# PWM_CON_CPU.net
KiCad netlist of a schematic drawn in Altium Designer
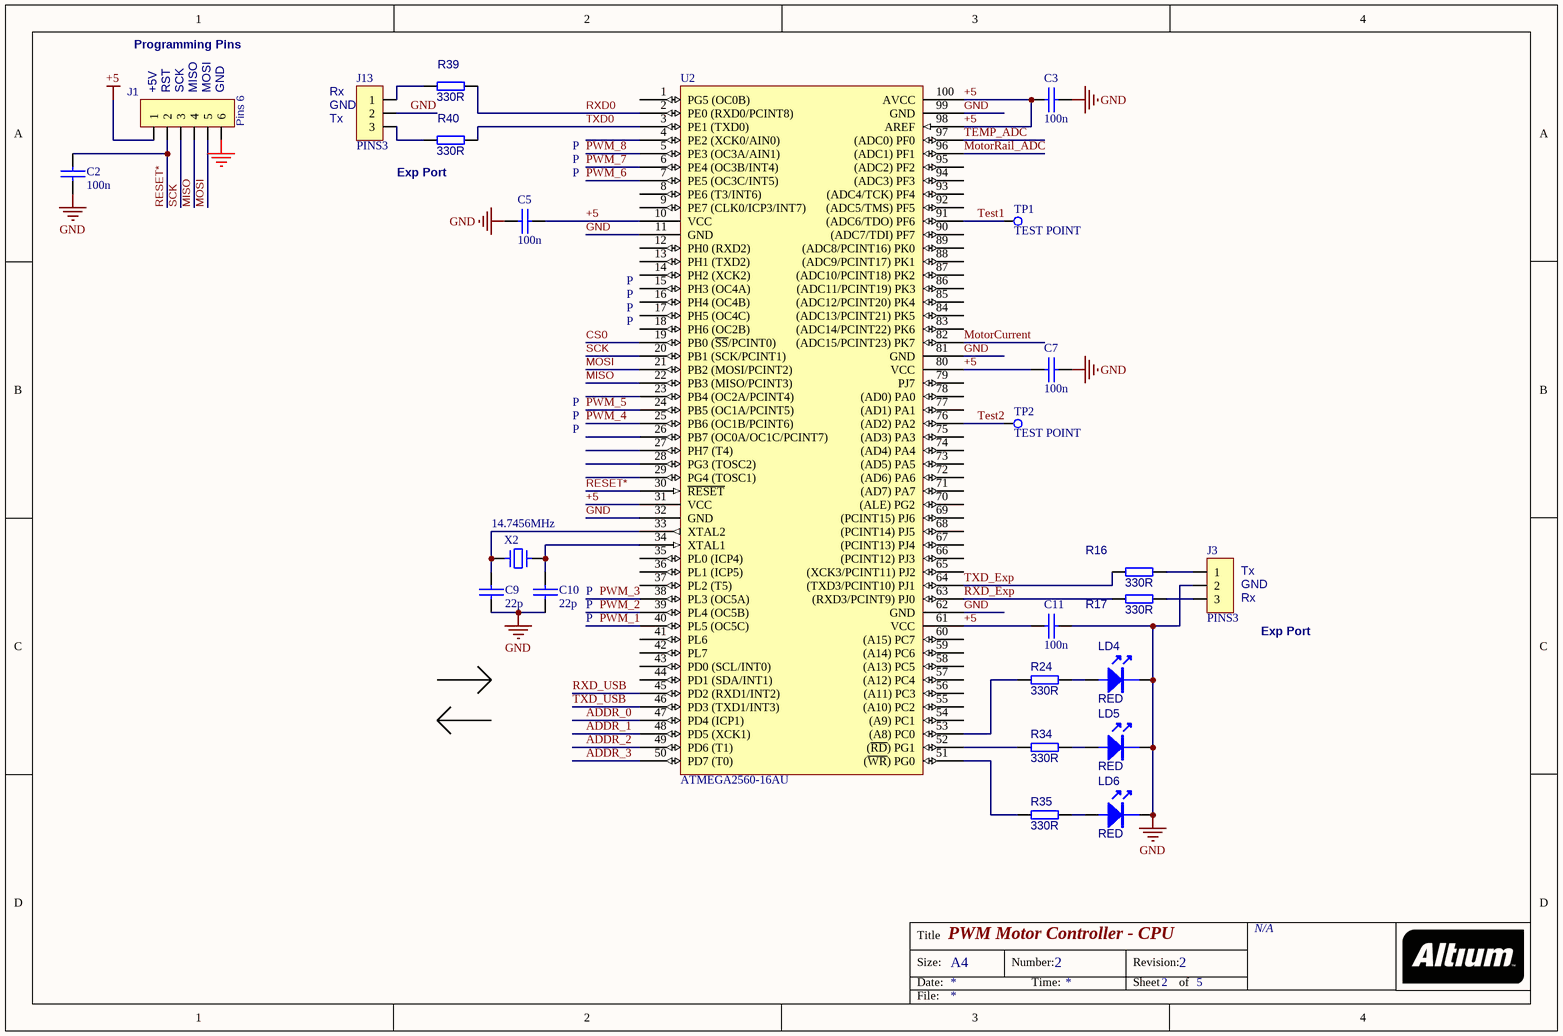
[diagram p0: PWM_CON_CPU.SchDoc]

(export (version "E")
  (design (tool "Eeschema 10.0.6"))
  (components
    (comp (ref "C2")
      (value "100n")
      (footprint "0603")
      (fields (field (name "PARTNO") "R8835"))
      (libsource (lib "*") (part "CAP"))
    )
    (comp (ref "C3")
      (value "100n")
      (footprint "0603")
      (fields (field (name "PARTNO") "R8835"))
      (libsource (lib "*") (part "CAP"))
    )
    (comp (ref "C5")
      (value "100n")
      (footprint "0603")
      (fields (field (name "PARTNO") "R8835"))
      (libsource (lib "*") (part "CAP"))
    )
    (comp (ref "C7")
      (value "100n")
      (footprint "0603")
      (fields (field (name "PARTNO") "R8835"))
      (libsource (lib "*") (part "CAP"))
    )
    (comp (ref "C9")
      (value "22p")
      (footprint "0603")
      (fields (field (name "PARTNO") "R8736"))
      (libsource (lib "DEVICE") (part "CAP"))
    )
    (comp (ref "C10")
      (value "22p")
      (footprint "0603")
      (fields (field (name "PARTNO") "R8736"))
      (libsource (lib "DEVICE") (part "CAP"))
    )
    (comp (ref "C11")
      (value "100n")
      (footprint "0603")
      (fields (field (name "PARTNO") "R8835"))
      (libsource (lib "*") (part "CAP"))
    )
    (comp (ref "J1")
      (value "Pins 6")
      (footprint "SIP6")
      (fields (field (name "PARTNO") "P5430"))
      (libsource (lib "*") (part "CON6"))
    )
    (comp (ref "J3")
      (value "PINS3")
      (footprint "SIP3")
      (fields (field (name "PARTNO") "P5430"))
      (libsource (lib "") (part "CON3_1"))
    )
    (comp (ref "J13")
      (value "PINS3")
      (footprint "SIP3")
      (fields (field (name "PARTNO") "P5430"))
      (libsource (lib "DEVICE") (part "CON3"))
    )
    (comp (ref "LD4")
      (value "RED")
      (footprint "0805DIODE")
      (fields (field (name "PARTNO") "Y1107"))
      (libsource (lib "*") (part "LED"))
    )
    (comp (ref "LD5")
      (value "RED")
      (footprint "0805DIODE")
      (fields (field (name "PARTNO") "Y1107"))
      (libsource (lib "*") (part "LED"))
    )
    (comp (ref "LD6")
      (value "RED")
      (footprint "0805DIODE")
      (fields (field (name "PARTNO") "Y1107"))
      (libsource (lib "*") (part "LED"))
    )
    (comp (ref "R16")
      (value "330R")
      (footprint "0603")
      (fields (field (name "PARTNO") "R1560"))
      (libsource (lib "DEVICE") (part "RES8"))
    )
    (comp (ref "R17")
      (value "330R")
      (footprint "0603")
      (fields (field (name "PARTNO") "R1560"))
      (libsource (lib "DEVICE") (part "RES8"))
    )
    (comp (ref "R24")
      (value "330R")
      (footprint "0603")
      (fields (field (name "PARTNO") "R1560"))
      (libsource (lib "DEVICE") (part "RES8"))
    )
    (comp (ref "R34")
      (value "330R")
      (footprint "0603")
      (fields (field (name "PARTNO") "R1560"))
      (libsource (lib "DEVICE") (part "RES8"))
    )
    (comp (ref "R35")
      (value "330R")
      (footprint "0603")
      (fields (field (name "PARTNO") "R1560"))
      (libsource (lib "DEVICE") (part "RES8"))
    )
    (comp (ref "R39")
      (value "330R")
      (footprint "0603")
      (fields (field (name "PARTNO") "R1560"))
      (libsource (lib "DEVICE") (part "RES8"))
    )
    (comp (ref "R40")
      (value "330R")
      (footprint "0603")
      (fields (field (name "PARTNO") "R1560"))
      (libsource (lib "DEVICE") (part "RES8"))
    )
    (comp (ref "TP1")
      (value "TEST POINT")
      (footprint "TEST POINT")
      (description "Probe compatible test point")
      (libsource (lib "DEVICE") (part "TEST POINT"))
    )
    (comp (ref "TP2")
      (value "TEST POINT")
      (footprint "TEST POINT")
      (description "Probe compatible test point")
      (libsource (lib "DEVICE") (part "TEST POINT"))
    )
    (comp (ref "U2")
      (value "ATMEGA2560-16AU")
      (footprint "100T1_N")
      (fields (field (name "PARTNO") "1288330"))
      (libsource (lib "Atmel") (part "ATMEGA2560(TQFP100)"))
    )
    (comp (ref "X2")
      (value "14.7456MHz")
      (footprint "XTAL-V2")
      (fields (field (name "PARTNO") "1640874"))
      (libsource (lib "DEVICE") (part "CRYSTAL"))
    )
  )
  (nets
    (net (code "1") (name "+5") (class "Default")
      (node (ref "C11") (pin "2") (pintype "passive"))
      (node (ref "C3") (pin "2") (pintype "passive"))
      (node (ref "C5") (pin "1") (pintype "passive"))
      (node (ref "C7") (pin "2") (pintype "passive"))
      (node (ref "J1") (pin "1") (pinfunction "1_1") (pintype "passive"))
      (node (ref "U2") (pin "10") (pinfunction "VCC_10") (pintype "power_in"))
      (node (ref "U2") (pin "100") (pinfunction "AVCC_100") (pintype "power_in"))
      (node (ref "U2") (pin "31") (pinfunction "VCC_31") (pintype "power_in"))
      (node (ref "U2") (pin "61") (pinfunction "VCC_61") (pintype "power_in"))
      (node (ref "U2") (pin "80") (pinfunction "VCC_80") (pintype "power_in"))
      (node (ref "U2") (pin "98") (pinfunction "AREF_98") (pintype "input"))
    )
    (net (code "2") (name "/ADDR_0") (class "Default")
      (node (ref "U2") (pin "47") (pinfunction "PD4_(ICP1)_47") (pintype "bidirectional"))
    )
    (net (code "3") (name "/ADDR_1") (class "Default")
      (node (ref "U2") (pin "48") (pinfunction "PD5_(XCK1)_48") (pintype "bidirectional"))
    )
    (net (code "4") (name "/ADDR_2") (class "Default")
      (node (ref "U2") (pin "49") (pinfunction "PD6_(T1)_49") (pintype "bidirectional"))
    )
    (net (code "5") (name "/ADDR_3") (class "Default")
      (node (ref "U2") (pin "50") (pinfunction "PD7_(T0)_50") (pintype "bidirectional"))
    )
    (net (code "6") (name "/CS0") (class "Default")
      (node (ref "U2") (pin "19") (pinfunction "PB0_(~{SS}/PCINT0)_19") (pintype "bidirectional"))
    )
    (net (code "7") (name "/MISO") (class "Default")
      (node (ref "J1") (pin "4") (pinfunction "4_4") (pintype "passive"))
      (node (ref "U2") (pin "22") (pinfunction "PB3_(MISO/PCINT3)_22") (pintype "bidirectional"))
    )
    (net (code "8") (name "/MOSI") (class "Default")
      (node (ref "J1") (pin "5") (pinfunction "5_5") (pintype "passive"))
      (node (ref "U2") (pin "21") (pinfunction "PB2_(MOSI/PCINT2)_21") (pintype "bidirectional"))
    )
    (net (code "9") (name "/MotorCurrent") (class "Default")
      (node (ref "U2") (pin "82") (pinfunction "(ADC15/PCINT23)_PK7_82") (pintype "bidirectional"))
    )
    (net (code "10") (name "/MotorRail_ADC") (class "Default")
      (node (ref "U2") (pin "96") (pinfunction "(ADC1)_PF1_96") (pintype "bidirectional"))
    )
    (net (code "11") (name "/PWM_1") (class "Default")
      (node (ref "U2") (pin "40") (pinfunction "PL5_(OC5C)_40") (pintype "bidirectional"))
    )
    (net (code "12") (name "/PWM_2") (class "Default")
      (node (ref "U2") (pin "39") (pinfunction "PL4_(OC5B)_39") (pintype "bidirectional"))
    )
    (net (code "13") (name "/PWM_3") (class "Default")
      (node (ref "U2") (pin "38") (pinfunction "PL3_(OC5A)_38") (pintype "bidirectional"))
    )
    (net (code "14") (name "/PWM_4") (class "Default")
      (node (ref "U2") (pin "25") (pinfunction "PB6_(OC1B/PCINT6)_25") (pintype "bidirectional"))
    )
    (net (code "15") (name "/PWM_5") (class "Default")
      (node (ref "U2") (pin "24") (pinfunction "PB5_(OC1A/PCINT5)_24") (pintype "bidirectional"))
    )
    (net (code "16") (name "/PWM_6") (class "Default")
      (node (ref "U2") (pin "7") (pinfunction "PE5_(OC3C/INT5)_7") (pintype "bidirectional"))
    )
    (net (code "17") (name "/PWM_7") (class "Default")
      (node (ref "U2") (pin "6") (pinfunction "PE4_(OC3B/INT4)_6") (pintype "bidirectional"))
    )
    (net (code "18") (name "/PWM_8") (class "Default")
      (node (ref "U2") (pin "5") (pinfunction "PE3_(OC3A/AIN1)_5") (pintype "bidirectional"))
    )
    (net (code "19") (name "/RESET*") (class "Default")
      (node (ref "C2") (pin "2") (pintype "passive"))
      (node (ref "J1") (pin "2") (pinfunction "2_2") (pintype "passive"))
      (node (ref "U2") (pin "30") (pinfunction "~{RESET}_30") (pintype "input"))
    )
    (net (code "20") (name "/RXD0") (class "Default")
      (node (ref "R39") (pin "2") (pintype "passive"))
      (node (ref "U2") (pin "2") (pinfunction "PE0_(RXD0/PCINT8)_2") (pintype "bidirectional"))
    )
    (net (code "21") (name "/RXD_Exp") (class "Default")
      (node (ref "R17") (pin "1") (pintype "passive"))
      (node (ref "U2") (pin "63") (pinfunction "(RXD3/PCINT9)_PJ0_63") (pintype "bidirectional"))
    )
    (net (code "22") (name "/RXD_USB") (class "Default")
      (node (ref "U2") (pin "45") (pinfunction "PD2_(RXD1/INT2)_45") (pintype "bidirectional"))
    )
    (net (code "23") (name "/SCK") (class "Default")
      (node (ref "J1") (pin "3") (pinfunction "3_3") (pintype "passive"))
      (node (ref "U2") (pin "20") (pinfunction "PB1_(SCK/PCINT1)_20") (pintype "bidirectional"))
    )
    (net (code "24") (name "/TEMP_ADC") (class "Default")
      (node (ref "U2") (pin "97") (pinfunction "(ADC0)_PF0_97") (pintype "bidirectional"))
    )
    (net (code "25") (name "/TXD0") (class "Default")
      (node (ref "R40") (pin "2") (pintype "passive"))
      (node (ref "U2") (pin "3") (pinfunction "PE1_(TXD0)_3") (pintype "bidirectional"))
    )
    (net (code "26") (name "/TXD_Exp") (class "Default")
      (node (ref "R16") (pin "1") (pintype "passive"))
      (node (ref "U2") (pin "64") (pinfunction "(TXD3/PCINT10)_PJ1_64") (pintype "bidirectional"))
    )
    (net (code "27") (name "/TXD_USB") (class "Default")
      (node (ref "U2") (pin "46") (pinfunction "PD3_(TXD1/INT3)_46") (pintype "bidirectional"))
    )
    (net (code "28") (name "/Test1") (class "Default")
      (node (ref "TP1") (pin "1") (pinfunction "1_1") (pintype "passive"))
      (node (ref "U2") (pin "91") (pinfunction "(ADC6/TDO)_PF6_91") (pintype "bidirectional"))
    )
    (net (code "29") (name "/Test2") (class "Default")
      (node (ref "TP2") (pin "1") (pinfunction "1_1") (pintype "passive"))
      (node (ref "U2") (pin "76") (pinfunction "(AD2)_PA2_76") (pintype "bidirectional"))
    )
    (net (code "30") (name "GND") (class "Default")
      (node (ref "C10") (pin "2") (pintype "passive"))
      (node (ref "C11") (pin "1") (pintype "passive"))
      (node (ref "C2") (pin "1") (pintype "passive"))
      (node (ref "C3") (pin "1") (pintype "passive"))
      (node (ref "C5") (pin "2") (pintype "passive"))
      (node (ref "C7") (pin "1") (pintype "passive"))
      (node (ref "C9") (pin "2") (pintype "passive"))
      (node (ref "J1") (pin "6") (pinfunction "6_6") (pintype "passive"))
      (node (ref "J13") (pin "2") (pinfunction "2_2") (pintype "passive"))
      (node (ref "J3") (pin "2") (pinfunction "2_2") (pintype "passive"))
      (node (ref "LD4") (pin "K") (pintype "passive"))
      (node (ref "LD5") (pin "K") (pintype "passive"))
      (node (ref "LD6") (pin "K") (pintype "passive"))
      (node (ref "U2") (pin "11") (pinfunction "GND_11") (pintype "power_in"))
      (node (ref "U2") (pin "32") (pinfunction "GND_32") (pintype "power_in"))
      (node (ref "U2") (pin "62") (pinfunction "GND_62") (pintype "power_in"))
      (node (ref "U2") (pin "81") (pinfunction "GND_81") (pintype "power_in"))
      (node (ref "U2") (pin "99") (pinfunction "GND_99") (pintype "power_in"))
    )
    (net (code "31") (name "Net-(J3-Pad1)") (class "Default")
      (node (ref "J3") (pin "1") (pinfunction "1_1") (pintype "passive"))
      (node (ref "R16") (pin "2") (pintype "passive"))
    )
    (net (code "32") (name "Net-(J3-Pad3)") (class "Default")
      (node (ref "J3") (pin "3") (pinfunction "3_3") (pintype "passive"))
      (node (ref "R17") (pin "2") (pintype "passive"))
    )
    (net (code "33") (name "Net-(J13-Pad1)") (class "Default")
      (node (ref "J13") (pin "1") (pinfunction "1_1") (pintype "passive"))
      (node (ref "R39") (pin "1") (pintype "passive"))
    )
    (net (code "34") (name "Net-(J13-Pad3)") (class "Default")
      (node (ref "J13") (pin "3") (pinfunction "3_3") (pintype "passive"))
      (node (ref "R40") (pin "1") (pintype "passive"))
    )
    (net (code "35") (name "Net-(LD4-PadA)") (class "Default")
      (node (ref "LD4") (pin "A") (pintype "passive"))
      (node (ref "R24") (pin "2") (pintype "passive"))
    )
    (net (code "36") (name "Net-(LD5-PadA)") (class "Default")
      (node (ref "LD5") (pin "A") (pintype "passive"))
      (node (ref "R34") (pin "2") (pintype "passive"))
    )
    (net (code "37") (name "Net-(LD6-PadA)") (class "Default")
      (node (ref "LD6") (pin "A") (pintype "passive"))
      (node (ref "R35") (pin "2") (pintype "passive"))
    )
    (net (code "38") (name "Net-(U2-(A8)_PC0)") (class "Default")
      (node (ref "R24") (pin "1") (pintype "passive"))
      (node (ref "U2") (pin "53") (pinfunction "(A8)_PC0_53") (pintype "bidirectional"))
    )
    (net (code "39") (name "Net-(U2-(~{RD})_PG1)") (class "Default")
      (node (ref "R34") (pin "1") (pintype "passive"))
      (node (ref "U2") (pin "52") (pinfunction "(~{RD})_PG1_52") (pintype "bidirectional"))
    )
    (net (code "40") (name "Net-(U2-(~{WR})_PG0)") (class "Default")
      (node (ref "R35") (pin "1") (pintype "passive"))
      (node (ref "U2") (pin "51") (pinfunction "(~{WR})_PG0_51") (pintype "bidirectional"))
    )
    (net (code "41") (name "Net-(U2-XTAL1)") (class "Default")
      (node (ref "C10") (pin "1") (pintype "passive"))
      (node (ref "U2") (pin "34") (pinfunction "XTAL1_34") (pintype "input"))
      (node (ref "X2") (pin "1") (pintype "passive"))
    )
    (net (code "42") (name "Net-(U2-XTAL2)") (class "Default")
      (node (ref "C9") (pin "1") (pintype "passive"))
      (node (ref "U2") (pin "33") (pinfunction "XTAL2_33") (pintype "output"))
      (node (ref "X2") (pin "2") (pintype "passive"))
    )
    (net (code "43") (name "unconnected-(U2-(A9)_PC1-Pad54)") (class "Default")
      (node (ref "U2") (pin "54") (pinfunction "(A9)_PC1_54") (pintype "bidirectional"))
    )
    (net (code "44") (name "unconnected-(U2-(A10)_PC2-Pad55)") (class "Default")
      (node (ref "U2") (pin "55") (pinfunction "(A10)_PC2_55") (pintype "bidirectional"))
    )
    (net (code "45") (name "unconnected-(U2-(A11)_PC3-Pad56)") (class "Default")
      (node (ref "U2") (pin "56") (pinfunction "(A11)_PC3_56") (pintype "bidirectional"))
    )
    (net (code "46") (name "unconnected-(U2-(A12)_PC4-Pad57)") (class "Default")
      (node (ref "U2") (pin "57") (pinfunction "(A12)_PC4_57") (pintype "bidirectional"))
    )
    (net (code "47") (name "unconnected-(U2-(A13)_PC5-Pad58)") (class "Default")
      (node (ref "U2") (pin "58") (pinfunction "(A13)_PC5_58") (pintype "bidirectional"))
    )
    (net (code "48") (name "unconnected-(U2-(A14)_PC6-Pad59)") (class "Default")
      (node (ref "U2") (pin "59") (pinfunction "(A14)_PC6_59") (pintype "bidirectional"))
    )
    (net (code "49") (name "unconnected-(U2-(A15)_PC7-Pad60)") (class "Default")
      (node (ref "U2") (pin "60") (pinfunction "(A15)_PC7_60") (pintype "bidirectional"))
    )
    (net (code "50") (name "unconnected-(U2-(AD0)_PA0-Pad78)") (class "Default")
      (node (ref "U2") (pin "78") (pinfunction "(AD0)_PA0_78") (pintype "bidirectional"))
    )
    (net (code "51") (name "unconnected-(U2-(AD1)_PA1-Pad77)") (class "Default")
      (node (ref "U2") (pin "77") (pinfunction "(AD1)_PA1_77") (pintype "bidirectional"))
    )
    (net (code "52") (name "unconnected-(U2-(AD3)_PA3-Pad75)") (class "Default")
      (node (ref "U2") (pin "75") (pinfunction "(AD3)_PA3_75") (pintype "bidirectional"))
    )
    (net (code "53") (name "unconnected-(U2-(AD4)_PA4-Pad74)") (class "Default")
      (node (ref "U2") (pin "74") (pinfunction "(AD4)_PA4_74") (pintype "bidirectional"))
    )
    (net (code "54") (name "unconnected-(U2-(AD5)_PA5-Pad73)") (class "Default")
      (node (ref "U2") (pin "73") (pinfunction "(AD5)_PA5_73") (pintype "bidirectional"))
    )
    (net (code "55") (name "unconnected-(U2-(AD6)_PA6-Pad72)") (class "Default")
      (node (ref "U2") (pin "72") (pinfunction "(AD6)_PA6_72") (pintype "bidirectional"))
    )
    (net (code "56") (name "unconnected-(U2-(AD7)_PA7-Pad71)") (class "Default")
      (node (ref "U2") (pin "71") (pinfunction "(AD7)_PA7_71") (pintype "bidirectional"))
    )
    (net (code "57") (name "unconnected-(U2-(ADC2)_PF2-Pad95)") (class "Default")
      (node (ref "U2") (pin "95") (pinfunction "(ADC2)_PF2_95") (pintype "bidirectional"))
    )
    (net (code "58") (name "unconnected-(U2-(ADC3)_PF3-Pad94)") (class "Default")
      (node (ref "U2") (pin "94") (pinfunction "(ADC3)_PF3_94") (pintype "bidirectional"))
    )
    (net (code "59") (name "unconnected-(U2-(ADC4{slash}TCK)_PF4-Pad93)") (class "Default")
      (node (ref "U2") (pin "93") (pinfunction "(ADC4/TCK)_PF4_93") (pintype "bidirectional"))
    )
    (net (code "60") (name "unconnected-(U2-(ADC5{slash}TMS)_PF5-Pad92)") (class "Default")
      (node (ref "U2") (pin "92") (pinfunction "(ADC5/TMS)_PF5_92") (pintype "bidirectional"))
    )
    (net (code "61") (name "unconnected-(U2-(ADC7{slash}TDI)_PF7-Pad90)") (class "Default")
      (node (ref "U2") (pin "90") (pinfunction "(ADC7/TDI)_PF7_90") (pintype "bidirectional"))
    )
    (net (code "62") (name "unconnected-(U2-(ADC8{slash}PCINT16)_PK0-Pad89)") (class "Default")
      (node (ref "U2") (pin "89") (pinfunction "(ADC8/PCINT16)_PK0_89") (pintype "bidirectional"))
    )
    (net (code "63") (name "unconnected-(U2-(ADC9{slash}PCINT17)_PK1-Pad88)") (class "Default")
      (node (ref "U2") (pin "88") (pinfunction "(ADC9/PCINT17)_PK1_88") (pintype "bidirectional"))
    )
    (net (code "64") (name "unconnected-(U2-(ADC10{slash}PCINT18)_PK2-Pad87)") (class "Default")
      (node (ref "U2") (pin "87") (pinfunction "(ADC10/PCINT18)_PK2_87") (pintype "bidirectional"))
    )
    (net (code "65") (name "unconnected-(U2-(ADC11{slash}PCINT19)_PK3-Pad86)") (class "Default")
      (node (ref "U2") (pin "86") (pinfunction "(ADC11/PCINT19)_PK3_86") (pintype "bidirectional"))
    )
    (net (code "66") (name "unconnected-(U2-(ADC12{slash}PCINT20)_PK4-Pad85)") (class "Default")
      (node (ref "U2") (pin "85") (pinfunction "(ADC12/PCINT20)_PK4_85") (pintype "bidirectional"))
    )
    (net (code "67") (name "unconnected-(U2-(ADC13{slash}PCINT21)_PK5-Pad84)") (class "Default")
      (node (ref "U2") (pin "84") (pinfunction "(ADC13/PCINT21)_PK5_84") (pintype "bidirectional"))
    )
    (net (code "68") (name "unconnected-(U2-(ADC14{slash}PCINT22)_PK6-Pad83)") (class "Default")
      (node (ref "U2") (pin "83") (pinfunction "(ADC14/PCINT22)_PK6_83") (pintype "bidirectional"))
    )
    (net (code "69") (name "unconnected-(U2-(ALE)_PG2-Pad70)") (class "Default")
      (node (ref "U2") (pin "70") (pinfunction "(ALE)_PG2_70") (pintype "bidirectional"))
    )
    (net (code "70") (name "unconnected-(U2-(PCINT12)_PJ3-Pad66)") (class "Default")
      (node (ref "U2") (pin "66") (pinfunction "(PCINT12)_PJ3_66") (pintype "bidirectional"))
    )
    (net (code "71") (name "unconnected-(U2-(PCINT13)_PJ4-Pad67)") (class "Default")
      (node (ref "U2") (pin "67") (pinfunction "(PCINT13)_PJ4_67") (pintype "bidirectional"))
    )
    (net (code "72") (name "unconnected-(U2-(PCINT14)_PJ5-Pad68)") (class "Default")
      (node (ref "U2") (pin "68") (pinfunction "(PCINT14)_PJ5_68") (pintype "bidirectional"))
    )
    (net (code "73") (name "unconnected-(U2-(PCINT15)_PJ6-Pad69)") (class "Default")
      (node (ref "U2") (pin "69") (pinfunction "(PCINT15)_PJ6_69") (pintype "bidirectional"))
    )
    (net (code "74") (name "unconnected-(U2-(XCK3{slash}PCINT11)_PJ2-Pad65)") (class "Default")
      (node (ref "U2") (pin "65") (pinfunction "(XCK3/PCINT11)_PJ2_65") (pintype "bidirectional"))
    )
    (net (code "75") (name "unconnected-(U2-PB4_(OC2A{slash}PCINT4)-Pad23)") (class "Default")
      (node (ref "U2") (pin "23") (pinfunction "PB4_(OC2A/PCINT4)_23") (pintype "bidirectional"))
    )
    (net (code "76") (name "unconnected-(U2-PB7_(OC0A{slash}OC1C{slash}PCINT7)-Pad26)") (class "Default")
      (node (ref "U2") (pin "26") (pinfunction "PB7_(OC0A/OC1C/PCINT7)_26") (pintype "bidirectional"))
    )
    (net (code "77") (name "unconnected-(U2-PD0_(SCL{slash}INT0)-Pad43)") (class "Default")
      (node (ref "U2") (pin "43") (pinfunction "PD0_(SCL/INT0)_43") (pintype "bidirectional"))
    )
    (net (code "78") (name "unconnected-(U2-PD1_(SDA{slash}INT1)-Pad44)") (class "Default")
      (node (ref "U2") (pin "44") (pinfunction "PD1_(SDA/INT1)_44") (pintype "bidirectional"))
    )
    (net (code "79") (name "unconnected-(U2-PE2_(XCK0{slash}AIN0)-Pad4)") (class "Default")
      (node (ref "U2") (pin "4") (pinfunction "PE2_(XCK0/AIN0)_4") (pintype "bidirectional"))
    )
    (net (code "80") (name "unconnected-(U2-PE6_(T3{slash}INT6)-Pad8)") (class "Default")
      (node (ref "U2") (pin "8") (pinfunction "PE6_(T3/INT6)_8") (pintype "bidirectional"))
    )
    (net (code "81") (name "unconnected-(U2-PE7_(CLK0{slash}ICP3{slash}INT7)-Pad9)") (class "Default")
      (node (ref "U2") (pin "9") (pinfunction "PE7_(CLK0/ICP3/INT7)_9") (pintype "bidirectional"))
    )
    (net (code "82") (name "unconnected-(U2-PG3_(TOSC2)-Pad28)") (class "Default")
      (node (ref "U2") (pin "28") (pinfunction "PG3_(TOSC2)_28") (pintype "bidirectional"))
    )
    (net (code "83") (name "unconnected-(U2-PG4_(TOSC1)-Pad29)") (class "Default")
      (node (ref "U2") (pin "29") (pinfunction "PG4_(TOSC1)_29") (pintype "bidirectional"))
    )
    (net (code "84") (name "unconnected-(U2-PG5_(OC0B)-Pad1)") (class "Default")
      (node (ref "U2") (pin "1") (pinfunction "PG5_(OC0B)_1") (pintype "bidirectional"))
    )
    (net (code "85") (name "unconnected-(U2-PH0_(RXD2)-Pad12)") (class "Default")
      (node (ref "U2") (pin "12") (pinfunction "PH0_(RXD2)_12") (pintype "bidirectional"))
    )
    (net (code "86") (name "unconnected-(U2-PH1_(TXD2)-Pad13)") (class "Default")
      (node (ref "U2") (pin "13") (pinfunction "PH1_(TXD2)_13") (pintype "bidirectional"))
    )
    (net (code "87") (name "unconnected-(U2-PH2_(XCK2)-Pad14)") (class "Default")
      (node (ref "U2") (pin "14") (pinfunction "PH2_(XCK2)_14") (pintype "bidirectional"))
    )
    (net (code "88") (name "unconnected-(U2-PH3_(OC4A)-Pad15)") (class "Default")
      (node (ref "U2") (pin "15") (pinfunction "PH3_(OC4A)_15") (pintype "bidirectional"))
    )
    (net (code "89") (name "unconnected-(U2-PH4_(OC4B)-Pad16)") (class "Default")
      (node (ref "U2") (pin "16") (pinfunction "PH4_(OC4B)_16") (pintype "bidirectional"))
    )
    (net (code "90") (name "unconnected-(U2-PH5_(OC4C)-Pad17)") (class "Default")
      (node (ref "U2") (pin "17") (pinfunction "PH5_(OC4C)_17") (pintype "bidirectional"))
    )
    (net (code "91") (name "unconnected-(U2-PH6_(OC2B)-Pad18)") (class "Default")
      (node (ref "U2") (pin "18") (pinfunction "PH6_(OC2B)_18") (pintype "bidirectional"))
    )
    (net (code "92") (name "unconnected-(U2-PH7_(T4)-Pad27)") (class "Default")
      (node (ref "U2") (pin "27") (pinfunction "PH7_(T4)_27") (pintype "bidirectional"))
    )
    (net (code "93") (name "unconnected-(U2-PJ7-Pad79)") (class "Default")
      (node (ref "U2") (pin "79") (pinfunction "PJ7_79") (pintype "bidirectional"))
    )
    (net (code "94") (name "unconnected-(U2-PL0_(ICP4)-Pad35)") (class "Default")
      (node (ref "U2") (pin "35") (pinfunction "PL0_(ICP4)_35") (pintype "bidirectional"))
    )
    (net (code "95") (name "unconnected-(U2-PL1_(ICP5)-Pad36)") (class "Default")
      (node (ref "U2") (pin "36") (pinfunction "PL1_(ICP5)_36") (pintype "bidirectional"))
    )
    (net (code "96") (name "unconnected-(U2-PL2_(T5)-Pad37)") (class "Default")
      (node (ref "U2") (pin "37") (pinfunction "PL2_(T5)_37") (pintype "bidirectional"))
    )
    (net (code "97") (name "unconnected-(U2-PL6-Pad41)") (class "Default")
      (node (ref "U2") (pin "41") (pinfunction "PL6_41") (pintype "bidirectional"))
    )
    (net (code "98") (name "unconnected-(U2-PL7-Pad42)") (class "Default")
      (node (ref "U2") (pin "42") (pinfunction "PL7_42") (pintype "bidirectional"))
    )
  )
)
